# Power_Supply.net
KiCad netlist of a schematic drawn in Altium Designer
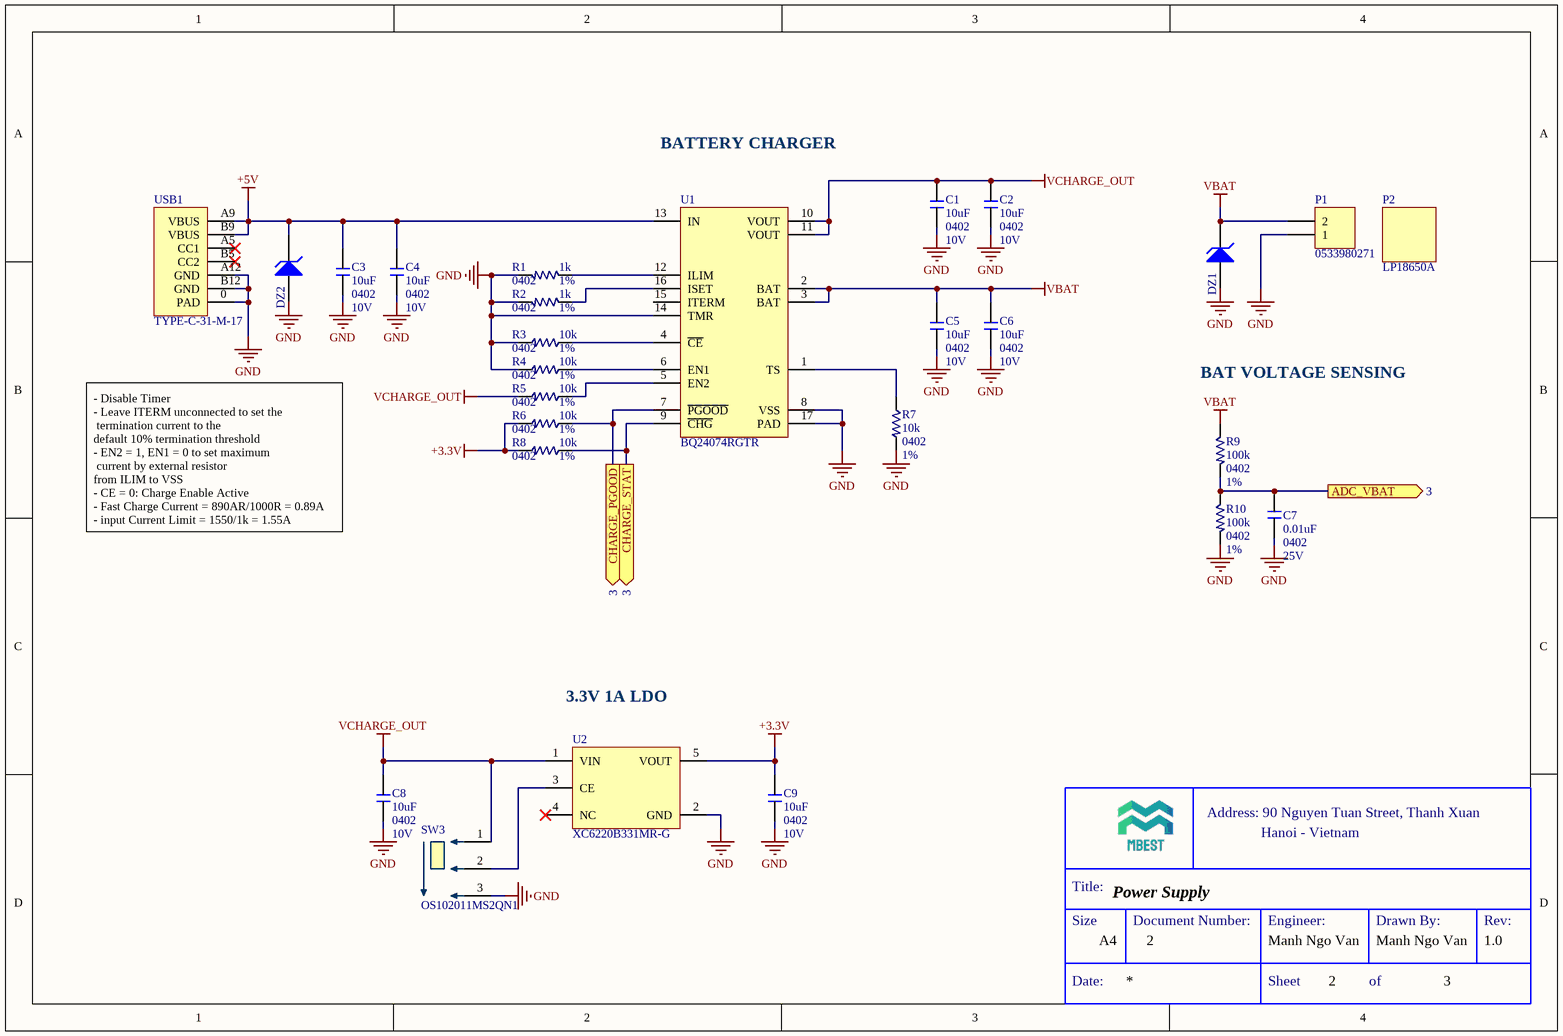
[diagram p0: Power Supply.SchDoc]

(export (version "E")
  (design (tool "Eeschema 10.0.6"))
  (components
    (comp (ref "C1")
      (value "10uF")
      (footprint "C0402M")
      (description "CAP CER 10UF 10V X5R 0402")
      (fields
        (field (name "CASE/PACKAGE") "0402")
        (field (name "VOLTAGE RATING") "10V")
        (field (name "TOLERANCE") "20%")
      )
      (libsource (lib "CommonLib") (part "CAP_CER"))
    )
    (comp (ref "C2")
      (value "10uF")
      (footprint "C0402M")
      (description "CAP CER 10UF 10V X5R 0402")
      (fields
        (field (name "CASE/PACKAGE") "0402")
        (field (name "VOLTAGE RATING") "10V")
        (field (name "TOLERANCE") "20%")
      )
      (libsource (lib "CommonLib") (part "CAP_CER"))
    )
    (comp (ref "C3")
      (value "10uF")
      (footprint "C0402M")
      (description "CAP CER 10UF 10V X5R 0402")
      (fields
        (field (name "CASE/PACKAGE") "0402")
        (field (name "VOLTAGE RATING") "10V")
        (field (name "TOLERANCE") "20%")
      )
      (libsource (lib "CommonLib") (part "CAP_CER"))
    )
    (comp (ref "C4")
      (value "10uF")
      (footprint "C0402M")
      (description "CAP CER 10UF 10V X5R 0402")
      (fields
        (field (name "CASE/PACKAGE") "0402")
        (field (name "VOLTAGE RATING") "10V")
        (field (name "TOLERANCE") "20%")
      )
      (libsource (lib "CommonLib") (part "CAP_CER"))
    )
    (comp (ref "C5")
      (value "10uF")
      (footprint "C0402M")
      (description "CAP CER 10UF 10V X5R 0402")
      (fields
        (field (name "CASE/PACKAGE") "0402")
        (field (name "VOLTAGE RATING") "10V")
        (field (name "TOLERANCE") "20%")
      )
      (libsource (lib "CommonLib") (part "CAP_CER"))
    )
    (comp (ref "C6")
      (value "10uF")
      (footprint "C0402M")
      (description "CAP CER 10UF 10V X5R 0402")
      (fields
        (field (name "CASE/PACKAGE") "0402")
        (field (name "VOLTAGE RATING") "10V")
        (field (name "TOLERANCE") "20%")
      )
      (libsource (lib "CommonLib") (part "CAP_CER"))
    )
    (comp (ref "C7")
      (value "0.01uF")
      (footprint "C0402M")
      (description "CAP CER 10000PF 25V X7R 0402")
      (fields
        (field (name "MANUFACTURER") "Samsung")
        (field (name "MANUFACTURER PART NUMBER") "CL05B103KA5NNNC")
        (field (name "CASE/PACKAGE") "0402")
        (field (name "VOLTAGE RATING") "25V")
      )
      (libsource (lib "") (part "CAP_CER_1"))
    )
    (comp (ref "C8")
      (value "10uF")
      (footprint "C0402M")
      (description "CAP CER 10UF 10V X5R 0402")
      (fields
        (field (name "CASE/PACKAGE") "0402")
        (field (name "VOLTAGE RATING") "10V")
        (field (name "TOLERANCE") "20%")
      )
      (libsource (lib "CommonLib") (part "CAP_CER"))
    )
    (comp (ref "C9")
      (value "10uF")
      (footprint "C0402M")
      (description "CAP CER 10UF 10V X5R 0402")
      (fields
        (field (name "CASE/PACKAGE") "0402")
        (field (name "VOLTAGE RATING") "10V")
        (field (name "TOLERANCE") "20%")
      )
      (libsource (lib "CommonLib") (part "CAP_CER"))
    )
    (comp (ref "DZ1")
      (value "TPD1E10B06DPYR")
      (footprint "R0402M")
      (description "TVS DIODE 5.5V 14V 2X1SON")
      (fields (field (name "MANUFACTURER") "Texas Instruments"))
      (libsource (lib "CommonLib") (part "D Zener"))
    )
    (comp (ref "DZ2")
      (value "TPD1E10B06DPYR")
      (footprint "R0402M")
      (description "TVS DIODE 5.5V 14V 2X1SON")
      (fields (field (name "MANUFACTURER") "Texas Instruments"))
      (libsource (lib "CommonLib") (part "D Zener"))
    )
    (comp (ref "P1")
      (value "0533980271")
      (footprint "0533980271")
      (description "CONN HEADER SMD 2POS 1.25MM")
      (fields (field (name "PUBLISHER") "Altium Limited"))
      (libsource (lib "Miscellaneous Connectors") (part "Header 2"))
    )
    (comp (ref "P2")
      (value "LP18650A")
      (description "3.7V Rechargeable Lithium-ion Polymer Battery LP18650A+ 3500mAh With PCM and JST Connector")
      (libsource (lib "CommonLib") (part "ADDITION"))
    )
    (comp (ref "R1")
      (value "1k")
      (footprint "R0402M")
      (description "RES SMD 1K OHM 1% 1/16W 0402")
      (fields (field (name "CASE/PACKAGE") "0402") (field (name "TOLERANCE") "1%"))
      (libsource (lib "CommonLib") (part "RES_SMD"))
    )
    (comp (ref "R2")
      (value "1k")
      (footprint "R0402M")
      (description "RES SMD 1K OHM 1% 1/16W 0402")
      (fields (field (name "CASE/PACKAGE") "0402") (field (name "TOLERANCE") "1%"))
      (libsource (lib "CommonLib") (part "RES_SMD"))
    )
    (comp (ref "R3")
      (value "10k")
      (footprint "R0402M")
      (description "RES SMD 10K OHM 1% 1/16W 0402")
      (fields
        (field (name "MANUFACTURER") "Yageo")
        (field (name "MANUFACTURER PART NUMBER") "RC0402FR-0710KL")
        (field (name "CASE CODE (IMPERIAL)") "0402")
        (field (name "TOLERANCE") "1%")
      )
      (libsource (lib "CommonLib") (part "RES_SMD"))
    )
    (comp (ref "R4")
      (value "10k")
      (footprint "R0402M")
      (description "RES SMD 10K OHM 1% 1/16W 0402")
      (fields
        (field (name "MANUFACTURER") "Yageo")
        (field (name "MANUFACTURER PART NUMBER") "RC0402FR-0710KL")
        (field (name "CASE CODE (IMPERIAL)") "0402")
        (field (name "TOLERANCE") "1%")
      )
      (libsource (lib "CommonLib") (part "RES_SMD"))
    )
    (comp (ref "R5")
      (value "10k")
      (footprint "R0402M")
      (description "RES SMD 10K OHM 1% 1/16W 0402")
      (fields
        (field (name "MANUFACTURER") "Yageo")
        (field (name "MANUFACTURER PART NUMBER") "RC0402FR-0710KL")
        (field (name "CASE CODE (IMPERIAL)") "0402")
        (field (name "TOLERANCE") "1%")
      )
      (libsource (lib "CommonLib") (part "RES_SMD"))
    )
    (comp (ref "R6")
      (value "10k")
      (footprint "R0402M")
      (description "RES SMD 10K OHM 1% 1/16W 0402")
      (fields
        (field (name "MANUFACTURER") "Yageo")
        (field (name "MANUFACTURER PART NUMBER") "RC0402FR-0710KL")
        (field (name "CASE CODE (IMPERIAL)") "0402")
        (field (name "TOLERANCE") "1%")
      )
      (libsource (lib "CommonLib") (part "RES_SMD"))
    )
    (comp (ref "R7")
      (value "10k")
      (footprint "R0402M")
      (description "RES SMD 10K OHM 1% 1/16W 0402")
      (fields
        (field (name "MANUFACTURER") "Yageo")
        (field (name "MANUFACTURER PART NUMBER") "RC0402FR-0710KL")
        (field (name "CASE CODE (IMPERIAL)") "0402")
        (field (name "TOLERANCE") "1%")
      )
      (libsource (lib "CommonLib") (part "RES_SMD"))
    )
    (comp (ref "R8")
      (value "10k")
      (footprint "R0402M")
      (description "RES SMD 10K OHM 1% 1/16W 0402")
      (fields
        (field (name "MANUFACTURER") "Yageo")
        (field (name "MANUFACTURER PART NUMBER") "RC0402FR-0710KL")
        (field (name "CASE CODE (IMPERIAL)") "0402")
        (field (name "TOLERANCE") "1%")
      )
      (libsource (lib "CommonLib") (part "RES_SMD"))
    )
    (comp (ref "R9")
      (value "100k")
      (footprint "R0402M")
      (description "RES SMD 100K OHM 1% 1/16W 0402")
      (fields
        (field (name "MANUFACTURER") "Yageo")
        (field (name "MANUFACTURER PART NUMBER") "RC0402FR-07100KL")
        (field (name "CASE/PACKAGE") "0402")
        (field (name "TOLERANCE") "1%")
      )
      (libsource (lib "BLE1") (part "RES_SMD"))
    )
    (comp (ref "R10")
      (value "100k")
      (footprint "R0402M")
      (description "RES SMD 100K OHM 1% 1/16W 0402")
      (fields
        (field (name "MANUFACTURER") "Yageo")
        (field (name "MANUFACTURER PART NUMBER") "RC0402FR-07100KL")
        (field (name "CASE/PACKAGE") "0402")
        (field (name "TOLERANCE") "1%")
      )
      (libsource (lib "BLE1") (part "RES_SMD"))
    )
    (comp (ref "SW3")
      (value "OS102011MS2QN1")
      (footprint "OS102011MS2QN1")
      (description "Slide")
      (libsource (lib "Poskast") (part "JS202011JAQN"))
    )
    (comp (ref "U1")
      (value "BQ24074RGTR")
      (footprint "QFN50P300X300X100_HS-17N")
      (description "IC BATT CHG LI-ION 1CELL 16QFN")
      (libsource (lib "SmartHome") (part "BQ24074RGTR"))
    )
    (comp (ref "U2")
      (value "XC6220B331MR-G")
      (footprint "SOT95P280X145-5NP")
      (description "IC REG LINEAR 3.3V 1A SOT25")
      (fields (field (name "MANUFACTURER") "Torex"))
      (libsource (lib "SmartHome") (part "XC6220B331MR-G"))
    )
    (comp (ref "USB1")
      (value "TYPE-C-31-M-17")
      (footprint "TYPE-C-31-M-17")
      (description "USB - Type C Female 6 USB Connectors RoHS")
      (libsource (lib "Galvanic") (part "TYPE-C-31-M-17"))
    )
  )
  (nets
    (net (code "1") (name "+3.3V") (class "Default")
      (node (ref "C9") (pin "2") (pinfunction "2_2") (pintype "passive"))
      (node (ref "R6") (pin "1") (pinfunction "1_1") (pintype "passive"))
      (node (ref "R8") (pin "1") (pinfunction "1_1") (pintype "passive"))
      (node (ref "U2") (pin "5") (pinfunction "VOUT_5") (pintype "passive"))
    )
    (net (code "2") (name "+5V") (class "Default")
      (node (ref "C3") (pin "2") (pinfunction "2_2") (pintype "passive"))
      (node (ref "C4") (pin "2") (pinfunction "2_2") (pintype "passive"))
      (node (ref "DZ2") (pin "2") (pinfunction "K_2") (pintype "passive"))
      (node (ref "U1") (pin "13") (pinfunction "IN_13") (pintype "passive"))
      (node (ref "USB1") (pin "A9") (pinfunction "VBUS_A9") (pintype "passive"))
      (node (ref "USB1") (pin "B9") (pinfunction "VBUS_B9") (pintype "passive"))
    )
    (net (code "3") (name "/ADC_VBAT") (class "Default")
      (node (ref "C7") (pin "2") (pinfunction "2_2") (pintype "passive"))
      (node (ref "R10") (pin "2") (pinfunction "2_2") (pintype "passive"))
      (node (ref "R9") (pin "1") (pinfunction "1_1") (pintype "passive"))
    )
    (net (code "4") (name "/CHARGE_PGOOD") (class "Default")
      (node (ref "R6") (pin "2") (pinfunction "2_2") (pintype "passive"))
      (node (ref "U1") (pin "7") (pinfunction "~{PGOOD}_7") (pintype "passive"))
    )
    (net (code "5") (name "/CHARGE_STAT") (class "Default")
      (node (ref "R8") (pin "2") (pinfunction "2_2") (pintype "passive"))
      (node (ref "U1") (pin "9") (pinfunction "~{CHG}_9") (pintype "passive"))
    )
    (net (code "6") (name "GND") (class "Default")
      (node (ref "C1") (pin "1") (pinfunction "1_1") (pintype "passive"))
      (node (ref "C2") (pin "1") (pinfunction "1_1") (pintype "passive"))
      (node (ref "C3") (pin "1") (pinfunction "1_1") (pintype "passive"))
      (node (ref "C4") (pin "1") (pinfunction "1_1") (pintype "passive"))
      (node (ref "C5") (pin "1") (pinfunction "1_1") (pintype "passive"))
      (node (ref "C6") (pin "1") (pinfunction "1_1") (pintype "passive"))
      (node (ref "C7") (pin "1") (pinfunction "1_1") (pintype "passive"))
      (node (ref "C8") (pin "1") (pinfunction "1_1") (pintype "passive"))
      (node (ref "C9") (pin "1") (pinfunction "1_1") (pintype "passive"))
      (node (ref "DZ1") (pin "1") (pinfunction "A_1") (pintype "passive"))
      (node (ref "DZ2") (pin "1") (pinfunction "A_1") (pintype "passive"))
      (node (ref "P1") (pin "1") (pinfunction "1_1") (pintype "passive"))
      (node (ref "R1") (pin "1") (pinfunction "1_1") (pintype "passive"))
      (node (ref "R10") (pin "1") (pinfunction "1_1") (pintype "passive"))
      (node (ref "R2") (pin "1") (pinfunction "1_1") (pintype "passive"))
      (node (ref "R3") (pin "1") (pinfunction "1_1") (pintype "passive"))
      (node (ref "R4") (pin "1") (pinfunction "1_1") (pintype "passive"))
      (node (ref "R7") (pin "1") (pinfunction "1_1") (pintype "passive"))
      (node (ref "SW3") (pin "3") (pinfunction "3_3") (pintype "passive"))
      (node (ref "U1") (pin "14") (pinfunction "TMR_14") (pintype "passive"))
      (node (ref "U1") (pin "17") (pinfunction "PAD_17") (pintype "passive"))
      (node (ref "U1") (pin "8") (pinfunction "VSS_8") (pintype "passive"))
      (node (ref "U2") (pin "2") (pinfunction "GND_2") (pintype "passive"))
      (node (ref "USB1") (pin "0") (pinfunction "PAD_0") (pintype "passive"))
      (node (ref "USB1") (pin "A12") (pinfunction "GND_A12") (pintype "passive"))
      (node (ref "USB1") (pin "B12") (pinfunction "GND_B12") (pintype "passive"))
    )
    (net (code "7") (name "Net-(U1-EN1)") (class "Default")
      (node (ref "R4") (pin "2") (pinfunction "2_2") (pintype "passive"))
      (node (ref "U1") (pin "6") (pinfunction "EN1_6") (pintype "passive"))
    )
    (net (code "8") (name "Net-(U1-EN2)") (class "Default")
      (node (ref "R5") (pin "2") (pinfunction "2_2") (pintype "passive"))
      (node (ref "U1") (pin "5") (pinfunction "EN2_5") (pintype "passive"))
    )
    (net (code "9") (name "Net-(U1-ILIM)") (class "Default")
      (node (ref "R1") (pin "2") (pinfunction "2_2") (pintype "passive"))
      (node (ref "U1") (pin "12") (pinfunction "ILIM_12") (pintype "passive"))
    )
    (net (code "10") (name "Net-(U1-ISET)") (class "Default")
      (node (ref "R2") (pin "2") (pinfunction "2_2") (pintype "passive"))
      (node (ref "U1") (pin "16") (pinfunction "ISET_16") (pintype "passive"))
    )
    (net (code "11") (name "Net-(U1-TS)") (class "Default")
      (node (ref "R7") (pin "2") (pinfunction "2_2") (pintype "passive"))
      (node (ref "U1") (pin "1") (pinfunction "TS_1") (pintype "passive"))
    )
    (net (code "12") (name "Net-(U1-~{CE})") (class "Default")
      (node (ref "R3") (pin "2") (pinfunction "2_2") (pintype "passive"))
      (node (ref "U1") (pin "4") (pinfunction "~{CE}_4") (pintype "passive"))
    )
    (net (code "13") (name "Net-(U2-CE)") (class "Default")
      (node (ref "SW3") (pin "2") (pinfunction "2_2") (pintype "passive"))
      (node (ref "U2") (pin "3") (pinfunction "CE_3") (pintype "passive"))
    )
    (net (code "14") (name "VBAT") (class "Default")
      (node (ref "C5") (pin "2") (pinfunction "2_2") (pintype "passive"))
      (node (ref "C6") (pin "2") (pinfunction "2_2") (pintype "passive"))
      (node (ref "DZ1") (pin "2") (pinfunction "K_2") (pintype "passive"))
      (node (ref "P1") (pin "2") (pinfunction "2_2") (pintype "passive"))
      (node (ref "R9") (pin "2") (pinfunction "2_2") (pintype "passive"))
      (node (ref "U1") (pin "2") (pinfunction "BAT_2") (pintype "passive"))
      (node (ref "U1") (pin "3") (pinfunction "BAT_3") (pintype "passive"))
    )
    (net (code "15") (name "VCHARGE_OUT") (class "Default")
      (node (ref "C1") (pin "2") (pinfunction "2_2") (pintype "passive"))
      (node (ref "C2") (pin "2") (pinfunction "2_2") (pintype "passive"))
      (node (ref "C8") (pin "2") (pinfunction "2_2") (pintype "passive"))
      (node (ref "R5") (pin "1") (pinfunction "1_1") (pintype "passive"))
      (node (ref "SW3") (pin "1") (pinfunction "1_1") (pintype "passive"))
      (node (ref "U1") (pin "10") (pinfunction "VOUT_10") (pintype "passive"))
      (node (ref "U1") (pin "11") (pinfunction "VOUT_11") (pintype "passive"))
      (node (ref "U2") (pin "1") (pinfunction "VIN_1") (pintype "passive"))
    )
    (net (code "16") (name "unconnected-(U1-ITERM-Pad15)") (class "Default")
      (node (ref "U1") (pin "15") (pinfunction "ITERM_15") (pintype "passive"))
    )
    (net (code "17") (name "unconnected-(U2-NC-Pad4)") (class "Default")
      (node (ref "U2") (pin "4") (pinfunction "NC_4") (pintype "passive+no_connect"))
    )
    (net (code "18") (name "unconnected-(USB1-CC1-PadA5)") (class "Default")
      (node (ref "USB1") (pin "A5") (pinfunction "CC1_A5") (pintype "passive+no_connect"))
    )
    (net (code "19") (name "unconnected-(USB1-CC2-PadB5)") (class "Default")
      (node (ref "USB1") (pin "B5") (pinfunction "CC2_B5") (pintype "passive+no_connect"))
    )
  )
)
